# nRF52833_MCU_simple.net
KiCad netlist of a schematic drawn in EAGLE
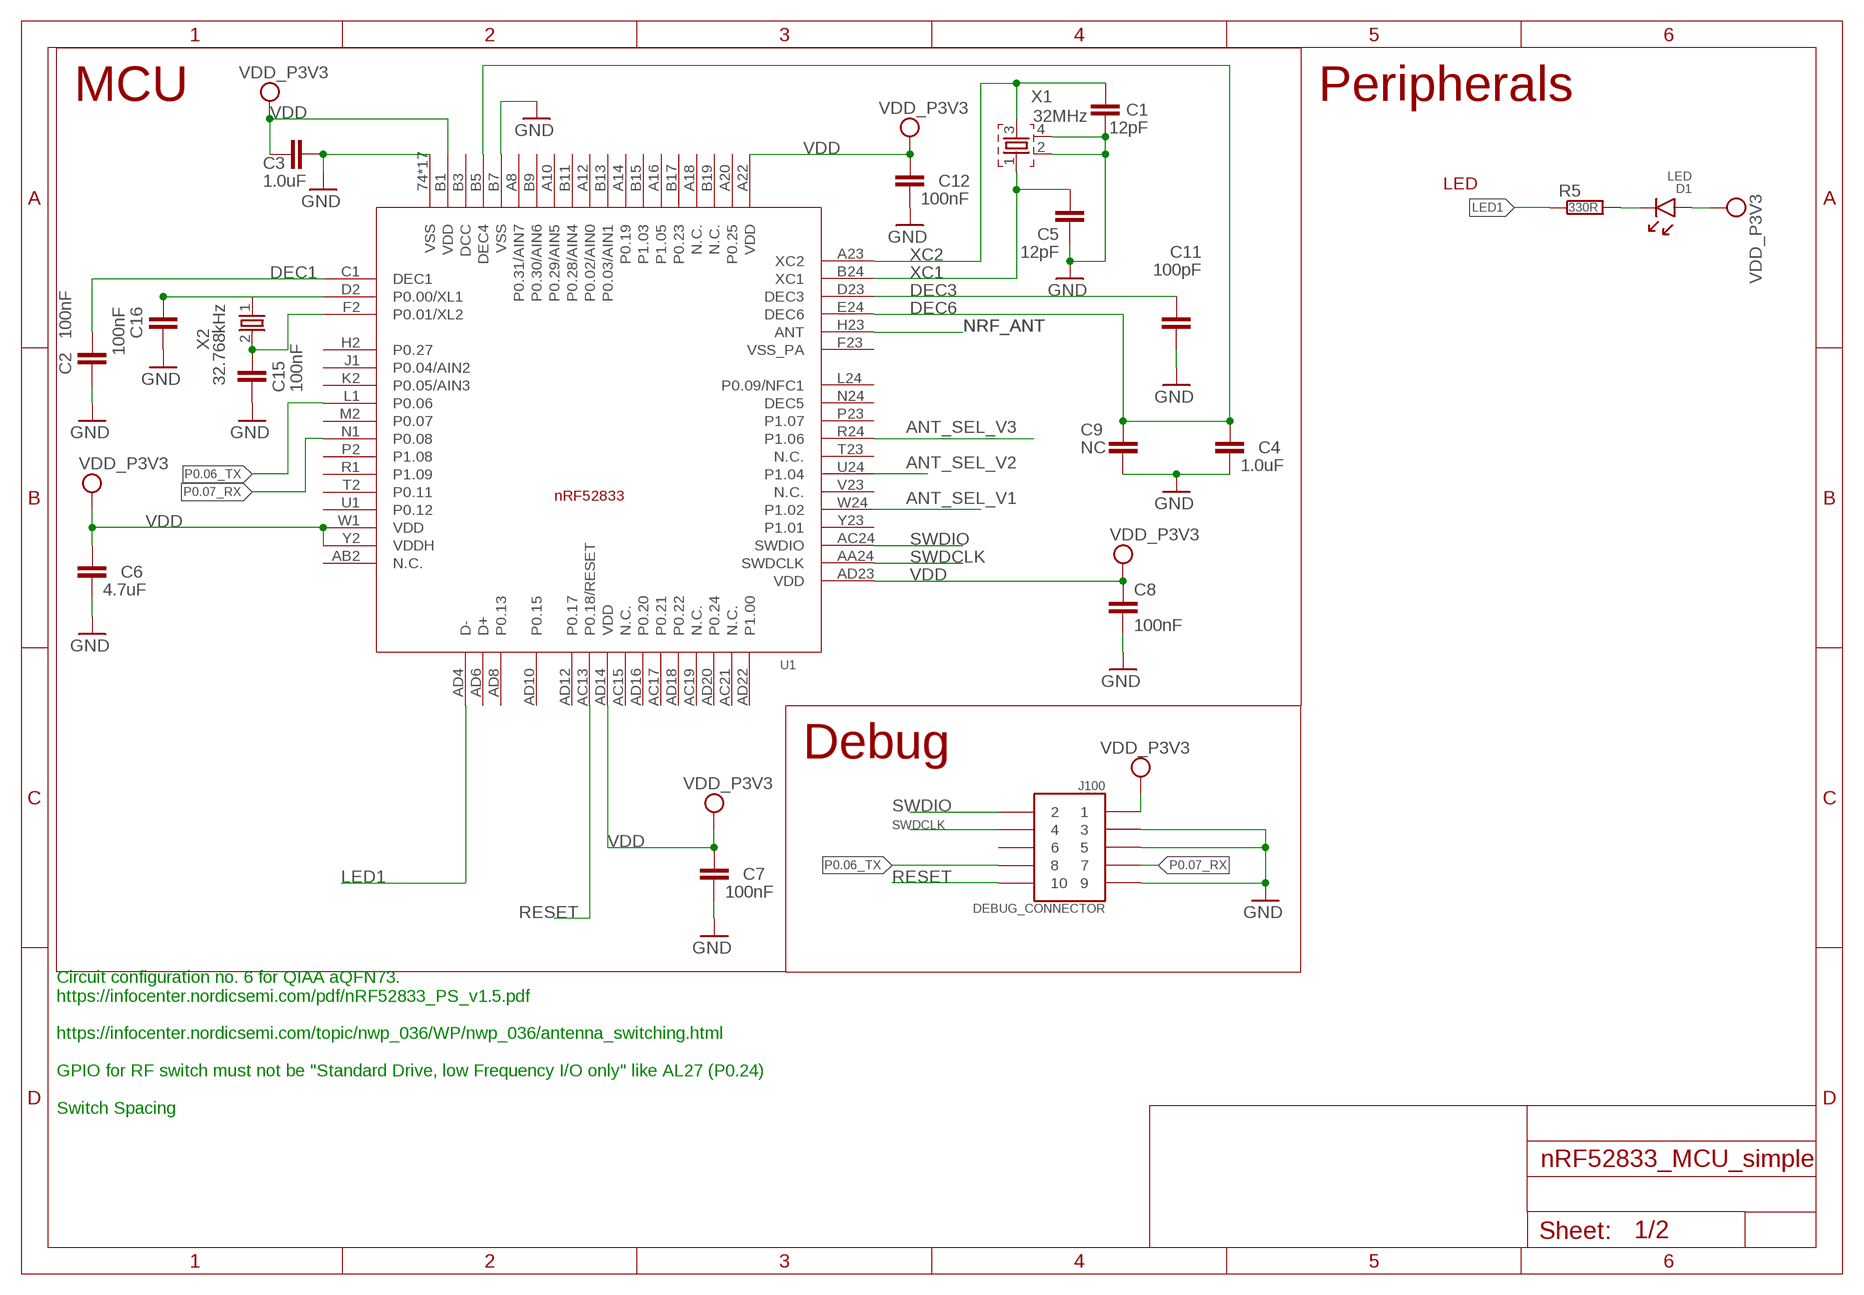
[diagram p0: schematic, sheet 1]
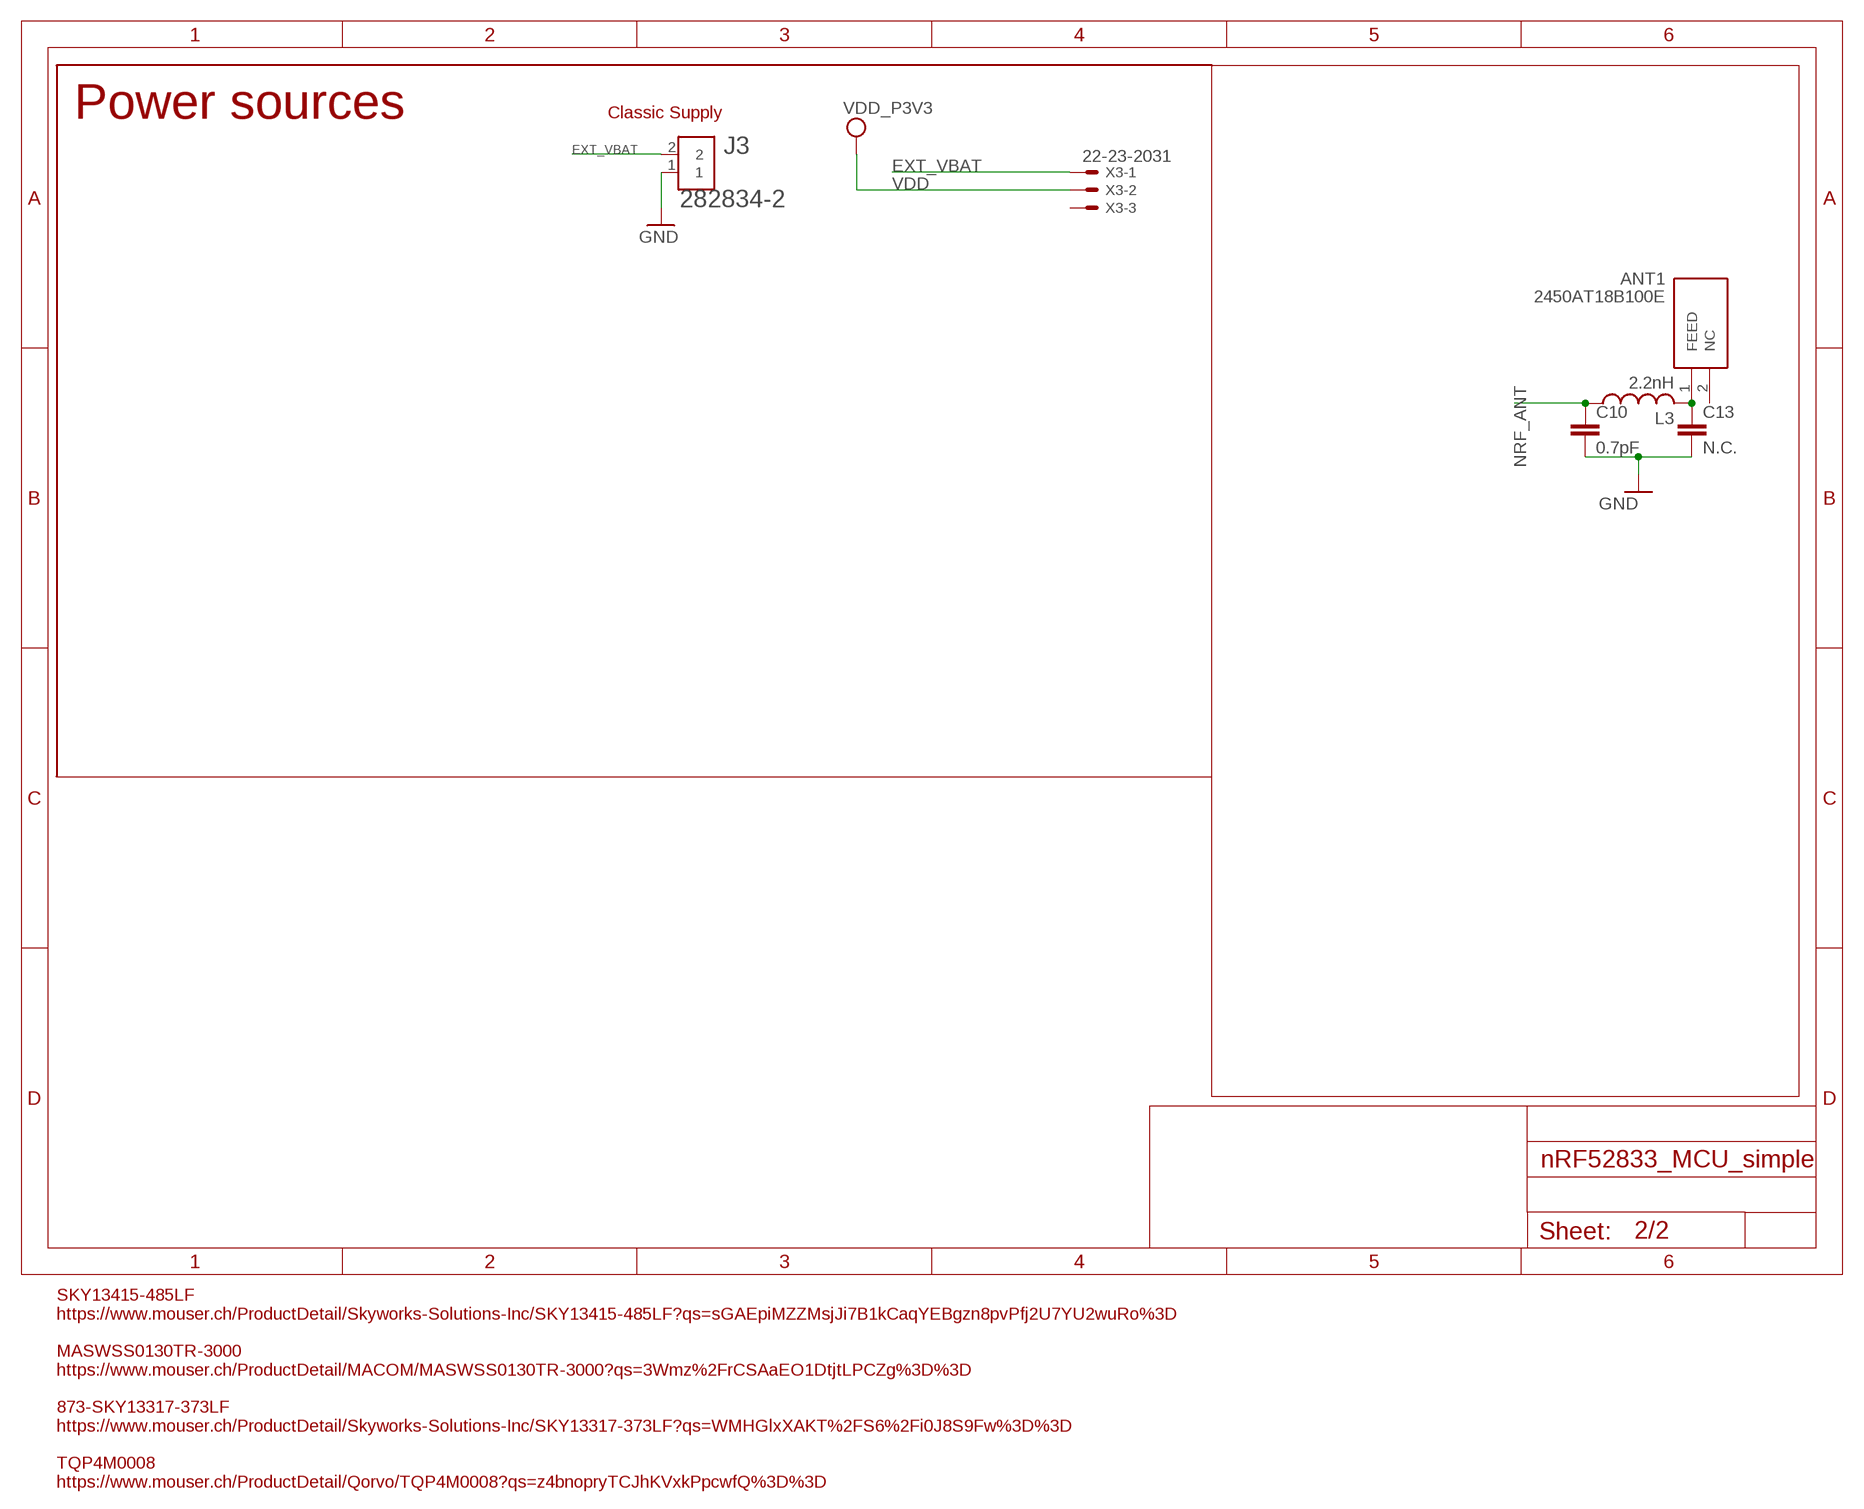
[diagram p1: schematic, sheet 2]

(export (version "E")
  (design (tool "Eeschema 10.0.6"))
  (components
    (comp (ref "C1")
      (value "12pF")
      (footprint "eagle-import:RESC0402_N")
      (libsource (lib "eagle-import") (part "CAPACITOR_0402_N"))
    )
    (comp (ref "C2")
      (value "100nF")
      (footprint "eagle-import:RESC0402_N")
      (libsource (lib "eagle-import") (part "CAPACITOR_0402_N"))
    )
    (comp (ref "C3")
      (value "1.0uF")
      (footprint "eagle-import:RESC0402_N")
      (libsource (lib "eagle-import") (part "CAPACITOR_0402_N"))
    )
    (comp (ref "C4")
      (value "1.0uF")
      (footprint "eagle-import:RESC0402_N")
      (libsource (lib "eagle-import") (part "CAPACITOR_0402_N"))
    )
    (comp (ref "C5")
      (value "12pF")
      (footprint "eagle-import:RESC0402_N")
      (libsource (lib "eagle-import") (part "CAPACITOR_0402_N"))
    )
    (comp (ref "C6")
      (value "4.7uF")
      (footprint "eagle-import:RESC0402_N")
      (libsource (lib "eagle-import") (part "CAPACITOR_0402_N"))
    )
    (comp (ref "C7")
      (value "100nF")
      (footprint "eagle-import:RESC0402_N")
      (libsource (lib "eagle-import") (part "CAPACITOR_0402_N"))
    )
    (comp (ref "C8")
      (value "100nF")
      (footprint "eagle-import:RESC0402_N")
      (libsource (lib "eagle-import") (part "CAPACITOR_0402_N"))
    )
    (comp (ref "C9")
      (value "NC")
      (footprint "eagle-import:RESC0402_N")
      (libsource (lib "eagle-import") (part "CAPACITOR_0402_N"))
    )
    (comp (ref "C11")
      (value "100pF")
      (footprint "eagle-import:RESC0402_N")
      (libsource (lib "eagle-import") (part "CAPACITOR_0402_N"))
    )
    (comp (ref "C12")
      (value "100nF")
      (footprint "eagle-import:RESC0402_N")
      (libsource (lib "eagle-import") (part "CAPACITOR_0402_N"))
    )
    (comp (ref "C15")
      (value "100nF")
      (footprint "eagle-import:RESC0402_N")
      (libsource (lib "eagle-import") (part "CAPACITOR_0402_N"))
    )
    (comp (ref "C16")
      (value "100nF")
      (footprint "eagle-import:RESC0402_N")
      (libsource (lib "eagle-import") (part "CAPACITOR_0402_N"))
    )
    (comp (ref "D1")
      (value "LED")
      (footprint "eagle-import:DIOC0603_N")
      (libsource (lib "eagle-import") (part "LED"))
    )
    (comp (ref "J100")
      (value "DEBUG_CONNECTOR")
      (footprint "eagle-import:HDRV127P5X2-10_N")
      (libsource (lib "eagle-import") (part "DEBUG_CONNECTOR"))
    )
    (comp (ref "R5")
      (value "330R")
      (footprint "eagle-import:RESC0402_N")
      (libsource (lib "eagle-import") (part "RESISTOR_0402_N"))
    )
    (comp (ref "U1")
      (value "nRF52833-QIAA")
      (footprint "eagle-import:AQFN50P700X700X85_HS-74N")
      (fields
        (field (name "MANUFACTURER") "Nordic Semiconductor")
        (field (name "PUBLISHER") "Nordic Semiconductor")
      )
      (libsource (lib "eagle-import") (part "NRF52833_QIAANRF52833_QIAA_AQFN50P700X700X85_HS-74N"))
    )
    (comp (ref "X1")
      (value "32MHz")
      (footprint "eagle-import:BT-XTAL_2016_N")
      (libsource (lib "eagle-import") (part "XTAL_32MHZ"))
    )
    (comp (ref "X2")
      (value "32.768kHz")
      (footprint "eagle-import:XTAL_3215_N")
      (libsource (lib "eagle-import") (part "XTAL_32KHZ"))
    )
    (comp (ref "ANT1")
      (value "2450AT18B100E")
      (footprint "eagle-import:ANTC3216X140N")
      (fields (field (name "MOUSER_PART_NUMBER") "609-2450AT18B100E"))
      (libsource (lib "eagle-import") (part "2450AT18B100E"))
    )
    (comp (ref "C10")
      (value "0.7pF")
      (footprint "eagle-import:RESC0402_N")
      (libsource (lib "eagle-import") (part "CAPACITOR_0402_N"))
    )
    (comp (ref "C13")
      (value "N.C.")
      (footprint "eagle-import:RESC0402_N")
      (libsource (lib "eagle-import") (part "CAPACITOR_0402_N"))
    )
    (comp (ref "J3")
      (value "282834-2")
      (footprint "eagle-import:CONN_282834-2")
      (fields (field (name "MF") "TE Connectivity"))
      (libsource (lib "eagle-import") (part "282834-2"))
    )
    (comp (ref "L3")
      (value "2.2nH")
      (footprint "eagle-import:RESC0402_N")
      (libsource (lib "eagle-import") (part "INDUCTOR_0402_N"))
    )
    (comp (ref "X3")
      (value "22-23-2031")
      (footprint "eagle-import:22-23-2031")
      (fields (field (name "MF") "MOLEX"))
      (libsource (lib "eagle-import") (part "22-23-2031"))
    )
  )
  (nets
    (net (code "1") (name "ANT_SEL_V1") (class "Default")
      (node (ref "U1") (pin "W24") (pinfunction "P1.02_W24") (pintype "bidirectional"))
    )
    (net (code "2") (name "ANT_SEL_V2") (class "Default")
      (node (ref "U1") (pin "U24") (pinfunction "P1.04_U24") (pintype "bidirectional"))
    )
    (net (code "3") (name "ANT_SEL_V3") (class "Default")
      (node (ref "U1") (pin "R24") (pinfunction "P1.06_R24") (pintype "bidirectional"))
    )
    (net (code "4") (name "DEC1") (class "Default")
      (node (ref "C2") (pin "1") (pinfunction "1_1") (pintype "passive"))
      (node (ref "U1") (pin "C1") (pinfunction "DEC1_C1") (pintype "power_in"))
    )
    (net (code "5") (name "DEC3") (class "Default")
      (node (ref "C11") (pin "1") (pinfunction "1_1") (pintype "passive"))
      (node (ref "U1") (pin "D23") (pinfunction "DEC3_D23") (pintype "power_in"))
    )
    (net (code "6") (name "DEC5") (class "Default")
      (node (ref "U1") (pin "N24") (pinfunction "DEC5_N24") (pintype "power_in"))
    )
    (net (code "7") (name "DEC6") (class "Default")
      (node (ref "C4") (pin "1") (pinfunction "1_1") (pintype "passive"))
      (node (ref "C9") (pin "1") (pinfunction "1_1") (pintype "passive"))
      (node (ref "U1") (pin "B5") (pinfunction "DEC4_B5") (pintype "power_in"))
      (node (ref "U1") (pin "E24") (pinfunction "DEC6_E24") (pintype "power_in"))
    )
    (net (code "8") (name "EXT_VBAT") (class "Default")
      (node (ref "J3") (pin "2") (pinfunction "2_2") (pintype "passive"))
      (node (ref "X3") (pin "1") (pinfunction "S_1") (pintype "passive"))
    )
    (net (code "9") (name "GND") (class "Default")
      (node (ref "C1") (pin "2") (pinfunction "2_2") (pintype "passive"))
      (node (ref "C10") (pin "2") (pinfunction "2_2") (pintype "passive"))
      (node (ref "C11") (pin "2") (pinfunction "2_2") (pintype "passive"))
      (node (ref "C12") (pin "2") (pinfunction "2_2") (pintype "passive"))
      (node (ref "C13") (pin "2") (pinfunction "2_2") (pintype "passive"))
      (node (ref "C15") (pin "1") (pinfunction "1_1") (pintype "passive"))
      (node (ref "C16") (pin "1") (pinfunction "1_1") (pintype "passive"))
      (node (ref "C2") (pin "2") (pinfunction "2_2") (pintype "passive"))
      (node (ref "C3") (pin "2") (pinfunction "2_2") (pintype "passive"))
      (node (ref "C4") (pin "2") (pinfunction "2_2") (pintype "passive"))
      (node (ref "C5") (pin "2") (pinfunction "2_2") (pintype "passive"))
      (node (ref "C6") (pin "2") (pinfunction "2_2") (pintype "passive"))
      (node (ref "C7") (pin "2") (pinfunction "2_2") (pintype "passive"))
      (node (ref "C8") (pin "2") (pinfunction "2_2") (pintype "passive"))
      (node (ref "C9") (pin "2") (pinfunction "2_2") (pintype "passive"))
      (node (ref "J100") (pin "3") (pinfunction "3_3") (pintype "bidirectional"))
      (node (ref "J100") (pin "5") (pinfunction "5_5") (pintype "bidirectional"))
      (node (ref "J100") (pin "9") (pinfunction "9_9") (pintype "bidirectional"))
      (node (ref "J3") (pin "1") (pinfunction "1_1") (pintype "passive"))
      (node (ref "U1") (pin "74") (pinfunction "VSS_74") (pintype "power_in"))
      (node (ref "U1") (pin "B7") (pinfunction "VSS_B7") (pintype "power_in"))
      (node (ref "U1") (pin "P$1") (pinfunction "VSS_P$1") (pintype "power_in"))
      (node (ref "U1") (pin "P$10") (pinfunction "VSS_P$10") (pintype "power_in"))
      (node (ref "U1") (pin "P$11") (pinfunction "VSS_P$11") (pintype "power_in"))
      (node (ref "U1") (pin "P$12") (pinfunction "VSS_P$12") (pintype "power_in"))
      (node (ref "U1") (pin "P$13") (pinfunction "VSS_P$13") (pintype "power_in"))
      (node (ref "U1") (pin "P$14") (pinfunction "VSS_P$14") (pintype "power_in"))
      (node (ref "U1") (pin "P$15") (pinfunction "VSS_P$15") (pintype "power_in"))
      (node (ref "U1") (pin "P$16") (pinfunction "VSS_P$16") (pintype "power_in"))
      (node (ref "U1") (pin "P$17") (pinfunction "VSS_P$17") (pintype "power_in"))
      (node (ref "U1") (pin "P$18") (pinfunction "VSS_P$18") (pintype "power_in"))
      (node (ref "U1") (pin "P$19") (pinfunction "VSS_P$19") (pintype "power_in"))
      (node (ref "U1") (pin "P$2") (pinfunction "VSS_P$2") (pintype "power_in"))
      (node (ref "U1") (pin "P$20") (pinfunction "VSS_P$20") (pintype "power_in"))
      (node (ref "U1") (pin "P$3") (pinfunction "VSS_P$3") (pintype "power_in"))
      (node (ref "U1") (pin "P$4") (pinfunction "VSS_P$4") (pintype "power_in"))
      (node (ref "U1") (pin "P$5") (pinfunction "VSS_P$5") (pintype "power_in"))
      (node (ref "X1") (pin "2") (pinfunction "2_2") (pintype "passive"))
      (node (ref "X1") (pin "4") (pinfunction "4_4") (pintype "passive"))
    )
    (net (code "10") (name "LED1") (class "Default")
      (node (ref "R5") (pin "1") (pinfunction "1_1") (pintype "passive"))
      (node (ref "U1") (pin "AD4") (pinfunction "D-_AD4") (pintype "bidirectional"))
    )
    (net (code "11") (name "NRF_ANT") (class "Default")
      (node (ref "C10") (pin "1") (pinfunction "1_1") (pintype "passive"))
      (node (ref "L3") (pin "1") (pinfunction "1_1") (pintype "passive"))
      (node (ref "U1") (pin "H23") (pinfunction "ANT_H23") (pintype "bidirectional"))
    )
    (net (code "12") (name "Net-(ANT1-FEED)") (class "Default")
      (node (ref "ANT1") (pin "1") (pinfunction "FEED_1") (pintype "input"))
      (node (ref "C13") (pin "1") (pinfunction "1_1") (pintype "passive"))
      (node (ref "L3") (pin "2") (pinfunction "2_2") (pintype "passive"))
    )
    (net (code "13") (name "Net-(D1-C)") (class "Default")
      (node (ref "D1") (pin "1") (pinfunction "C_1") (pintype "bidirectional"))
      (node (ref "R5") (pin "2") (pinfunction "2_2") (pintype "passive"))
    )
    (net (code "14") (name "Net-(U1-P0.00{slash}XL1)") (class "Default")
      (node (ref "C16") (pin "2") (pinfunction "2_2") (pintype "passive"))
      (node (ref "U1") (pin "D2") (pinfunction "P0.00/XL1_D2") (pintype "bidirectional"))
      (node (ref "X2") (pin "1") (pinfunction "1_1") (pintype "passive"))
    )
    (net (code "15") (name "Net-(U1-P0.01{slash}XL2)") (class "Default")
      (node (ref "C15") (pin "2") (pinfunction "2_2") (pintype "passive"))
      (node (ref "U1") (pin "F2") (pinfunction "P0.01/XL2_F2") (pintype "bidirectional"))
      (node (ref "X2") (pin "2") (pinfunction "2_2") (pintype "passive"))
    )
    (net (code "16") (name "P0.06_TX") (class "Default")
      (node (ref "J100") (pin "8") (pinfunction "8_8") (pintype "bidirectional"))
      (node (ref "U1") (pin "L1") (pinfunction "P0.06_L1") (pintype "bidirectional"))
    )
    (net (code "17") (name "P0.07_RX") (class "Default")
      (node (ref "J100") (pin "7") (pinfunction "7_7") (pintype "bidirectional"))
      (node (ref "U1") (pin "N1") (pinfunction "P0.08_N1") (pintype "bidirectional"))
    )
    (net (code "18") (name "RESET") (class "Default")
      (node (ref "J100") (pin "10") (pinfunction "10_10") (pintype "bidirectional"))
      (node (ref "U1") (pin "AC13") (pinfunction "P0.18/RESET_AC13") (pintype "bidirectional"))
    )
    (net (code "19") (name "SWDCLK") (class "Default")
      (node (ref "J100") (pin "4") (pinfunction "4_4") (pintype "bidirectional"))
      (node (ref "U1") (pin "AA24") (pinfunction "SWDCLK_AA24") (pintype "input"))
    )
    (net (code "20") (name "SWDIO") (class "Default")
      (node (ref "J100") (pin "2") (pinfunction "2_2") (pintype "bidirectional"))
      (node (ref "U1") (pin "AC24") (pinfunction "SWDIO_AC24") (pintype "bidirectional"))
    )
    (net (code "21") (name "VDD") (class "Default")
      (node (ref "C12") (pin "1") (pinfunction "1_1") (pintype "passive"))
      (node (ref "C3") (pin "1") (pinfunction "1_1") (pintype "passive"))
      (node (ref "C6") (pin "1") (pinfunction "1_1") (pintype "passive"))
      (node (ref "C7") (pin "1") (pinfunction "1_1") (pintype "passive"))
      (node (ref "C8") (pin "1") (pinfunction "1_1") (pintype "passive"))
      (node (ref "D1") (pin "2") (pinfunction "A_2") (pintype "bidirectional"))
      (node (ref "J100") (pin "1") (pinfunction "1_1") (pintype "bidirectional"))
      (node (ref "U1") (pin "A22") (pinfunction "VDD_A22") (pintype "power_in"))
      (node (ref "U1") (pin "AD14") (pinfunction "VDD_AD14") (pintype "power_in"))
      (node (ref "U1") (pin "AD23") (pinfunction "VDD_AD23") (pintype "power_in"))
      (node (ref "U1") (pin "B1") (pinfunction "VDD_B1") (pintype "power_in"))
      (node (ref "U1") (pin "W1") (pinfunction "VDD_W1") (pintype "power_in"))
      (node (ref "U1") (pin "Y2") (pinfunction "VDDH_Y2") (pintype "power_in"))
      (node (ref "X3") (pin "2") (pinfunction "S_2") (pintype "passive"))
    )
    (net (code "22") (name "VSS_PA") (class "Default")
      (node (ref "U1") (pin "F23") (pinfunction "VSS_PA_F23") (pintype "power_in"))
    )
    (net (code "23") (name "XC1") (class "Default")
      (node (ref "C5") (pin "1") (pinfunction "1_1") (pintype "passive"))
      (node (ref "U1") (pin "B24") (pinfunction "XC1_B24") (pintype "input"))
      (node (ref "X1") (pin "1") (pinfunction "1_1") (pintype "passive"))
    )
    (net (code "24") (name "XC2") (class "Default")
      (node (ref "C1") (pin "1") (pinfunction "1_1") (pintype "passive"))
      (node (ref "U1") (pin "A23") (pinfunction "XC2_A23") (pintype "output"))
      (node (ref "X1") (pin "3") (pinfunction "3_3") (pintype "passive"))
    )
    (net (code "25") (name "unconnected-(ANT1-NC-Pad2)") (class "Default")
      (node (ref "ANT1") (pin "2") (pinfunction "NC_2") (pintype "no_connect"))
    )
    (net (code "26") (name "unconnected-(J100-Pad6)") (class "Default")
      (node (ref "J100") (pin "6") (pinfunction "6_6") (pintype "bidirectional"))
    )
    (net (code "27") (name "unconnected-(U1-D+-PadAD6)") (class "Default")
      (node (ref "U1") (pin "AD6") (pinfunction "D+_AD6") (pintype "bidirectional"))
    )
    (net (code "28") (name "unconnected-(U1-DCC-PadB3)") (class "Default")
      (node (ref "U1") (pin "B3") (pinfunction "DCC_B3") (pintype "output"))
    )
    (net (code "29") (name "unconnected-(U1-N.C.-PadA18)") (class "Default")
      (node (ref "U1") (pin "A18") (pinfunction "N.C._A18") (pintype "passive"))
    )
    (net (code "30") (name "unconnected-(U1-N.C.-PadAB2)") (class "Default")
      (node (ref "U1") (pin "AB2") (pinfunction "N.C._AB2") (pintype "passive"))
    )
    (net (code "31") (name "unconnected-(U1-N.C.-PadAC15)") (class "Default")
      (node (ref "U1") (pin "AC15") (pinfunction "N.C._AC15") (pintype "passive"))
    )
    (net (code "32") (name "unconnected-(U1-N.C.-PadAC19)") (class "Default")
      (node (ref "U1") (pin "AC19") (pinfunction "N.C._AC19") (pintype "passive"))
    )
    (net (code "33") (name "unconnected-(U1-N.C.-PadAC21)") (class "Default")
      (node (ref "U1") (pin "AC21") (pinfunction "N.C._AC21") (pintype "passive"))
    )
    (net (code "34") (name "unconnected-(U1-N.C.-PadB19)") (class "Default")
      (node (ref "U1") (pin "B19") (pinfunction "N.C._B19") (pintype "passive"))
    )
    (net (code "35") (name "unconnected-(U1-N.C.-PadT23)") (class "Default")
      (node (ref "U1") (pin "T23") (pinfunction "N.C._T23") (pintype "passive"))
    )
    (net (code "36") (name "unconnected-(U1-N.C.-PadV23)") (class "Default")
      (node (ref "U1") (pin "V23") (pinfunction "N.C._V23") (pintype "passive"))
    )
    (net (code "37") (name "unconnected-(U1-P0.02{slash}AIN0-PadA12)") (class "Default")
      (node (ref "U1") (pin "A12") (pinfunction "P0.02/AIN0_A12") (pintype "bidirectional"))
    )
    (net (code "38") (name "unconnected-(U1-P0.03{slash}AIN1-PadB13)") (class "Default")
      (node (ref "U1") (pin "B13") (pinfunction "P0.03/AIN1_B13") (pintype "bidirectional"))
    )
    (net (code "39") (name "unconnected-(U1-P0.04{slash}AIN2-PadJ1)") (class "Default")
      (node (ref "U1") (pin "J1") (pinfunction "P0.04/AIN2_J1") (pintype "bidirectional"))
    )
    (net (code "40") (name "unconnected-(U1-P0.05{slash}AIN3-PadK2)") (class "Default")
      (node (ref "U1") (pin "K2") (pinfunction "P0.05/AIN3_K2") (pintype "bidirectional"))
    )
    (net (code "41") (name "unconnected-(U1-P0.07-PadM2)") (class "Default")
      (node (ref "U1") (pin "M2") (pinfunction "P0.07_M2") (pintype "bidirectional"))
    )
    (net (code "42") (name "unconnected-(U1-P0.09{slash}NFC1-PadL24)") (class "Default")
      (node (ref "U1") (pin "L24") (pinfunction "P0.09/NFC1_L24") (pintype "bidirectional"))
    )
    (net (code "43") (name "unconnected-(U1-P0.11-PadT2)") (class "Default")
      (node (ref "U1") (pin "T2") (pinfunction "P0.11_T2") (pintype "bidirectional"))
    )
    (net (code "44") (name "unconnected-(U1-P0.12-PadU1)") (class "Default")
      (node (ref "U1") (pin "U1") (pinfunction "P0.12_U1") (pintype "bidirectional"))
    )
    (net (code "45") (name "unconnected-(U1-P0.13-PadAD8)") (class "Default")
      (node (ref "U1") (pin "AD8") (pinfunction "P0.13_AD8") (pintype "bidirectional"))
    )
    (net (code "46") (name "unconnected-(U1-P0.15-PadAD10)") (class "Default")
      (node (ref "U1") (pin "AD10") (pinfunction "P0.15_AD10") (pintype "bidirectional"))
    )
    (net (code "47") (name "unconnected-(U1-P0.17-PadAD12)") (class "Default")
      (node (ref "U1") (pin "AD12") (pinfunction "P0.17_AD12") (pintype "bidirectional"))
    )
    (net (code "48") (name "unconnected-(U1-P0.19-PadA14)") (class "Default")
      (node (ref "U1") (pin "A14") (pinfunction "P0.19_A14") (pintype "bidirectional"))
    )
    (net (code "49") (name "unconnected-(U1-P0.20-PadAD16)") (class "Default")
      (node (ref "U1") (pin "AD16") (pinfunction "P0.20_AD16") (pintype "bidirectional"))
    )
    (net (code "50") (name "unconnected-(U1-P0.21-PadAC17)") (class "Default")
      (node (ref "U1") (pin "AC17") (pinfunction "P0.21_AC17") (pintype "bidirectional"))
    )
    (net (code "51") (name "unconnected-(U1-P0.22-PadAD18)") (class "Default")
      (node (ref "U1") (pin "AD18") (pinfunction "P0.22_AD18") (pintype "bidirectional"))
    )
    (net (code "52") (name "unconnected-(U1-P0.23-PadB17)") (class "Default")
      (node (ref "U1") (pin "B17") (pinfunction "P0.23_B17") (pintype "bidirectional"))
    )
    (net (code "53") (name "unconnected-(U1-P0.24-PadAD20)") (class "Default")
      (node (ref "U1") (pin "AD20") (pinfunction "P0.24_AD20") (pintype "bidirectional"))
    )
    (net (code "54") (name "unconnected-(U1-P0.25-PadA20)") (class "Default")
      (node (ref "U1") (pin "A20") (pinfunction "P0.25_A20") (pintype "bidirectional"))
    )
    (net (code "55") (name "unconnected-(U1-P0.27-PadH2)") (class "Default")
      (node (ref "U1") (pin "H2") (pinfunction "P0.27_H2") (pintype "bidirectional"))
    )
    (net (code "56") (name "unconnected-(U1-P0.28{slash}AIN4-PadB11)") (class "Default")
      (node (ref "U1") (pin "B11") (pinfunction "P0.28/AIN4_B11") (pintype "bidirectional"))
    )
    (net (code "57") (name "unconnected-(U1-P0.29{slash}AIN5-PadA10)") (class "Default")
      (node (ref "U1") (pin "A10") (pinfunction "P0.29/AIN5_A10") (pintype "bidirectional"))
    )
    (net (code "58") (name "unconnected-(U1-P0.30{slash}AIN6-PadB9)") (class "Default")
      (node (ref "U1") (pin "B9") (pinfunction "P0.30/AIN6_B9") (pintype "bidirectional"))
    )
    (net (code "59") (name "unconnected-(U1-P0.31{slash}AIN7-PadA8)") (class "Default")
      (node (ref "U1") (pin "A8") (pinfunction "P0.31/AIN7_A8") (pintype "bidirectional"))
    )
    (net (code "60") (name "unconnected-(U1-P1.00-PadAD22)") (class "Default")
      (node (ref "U1") (pin "AD22") (pinfunction "P1.00_AD22") (pintype "bidirectional"))
    )
    (net (code "61") (name "unconnected-(U1-P1.01-PadY23)") (class "Default")
      (node (ref "U1") (pin "Y23") (pinfunction "P1.01_Y23") (pintype "bidirectional"))
    )
    (net (code "62") (name "unconnected-(U1-P1.03-PadB15)") (class "Default")
      (node (ref "U1") (pin "B15") (pinfunction "P1.03_B15") (pintype "bidirectional"))
    )
    (net (code "63") (name "unconnected-(U1-P1.05-PadA16)") (class "Default")
      (node (ref "U1") (pin "A16") (pinfunction "P1.05_A16") (pintype "bidirectional"))
    )
    (net (code "64") (name "unconnected-(U1-P1.07-PadP23)") (class "Default")
      (node (ref "U1") (pin "P23") (pinfunction "P1.07_P23") (pintype "bidirectional"))
    )
    (net (code "65") (name "unconnected-(U1-P1.08-PadP2)") (class "Default")
      (node (ref "U1") (pin "P2") (pinfunction "P1.08_P2") (pintype "bidirectional"))
    )
    (net (code "66") (name "unconnected-(U1-P1.09-PadR1)") (class "Default")
      (node (ref "U1") (pin "R1") (pinfunction "P1.09_R1") (pintype "bidirectional"))
    )
    (net (code "67") (name "unconnected-(X3C-S-Pad3)") (class "Default")
      (node (ref "X3") (pin "3") (pinfunction "S_3") (pintype "passive"))
    )
  )
)
